# murdock_conn_v4.net
KiCad netlist of a schematic drawn in EAGLE
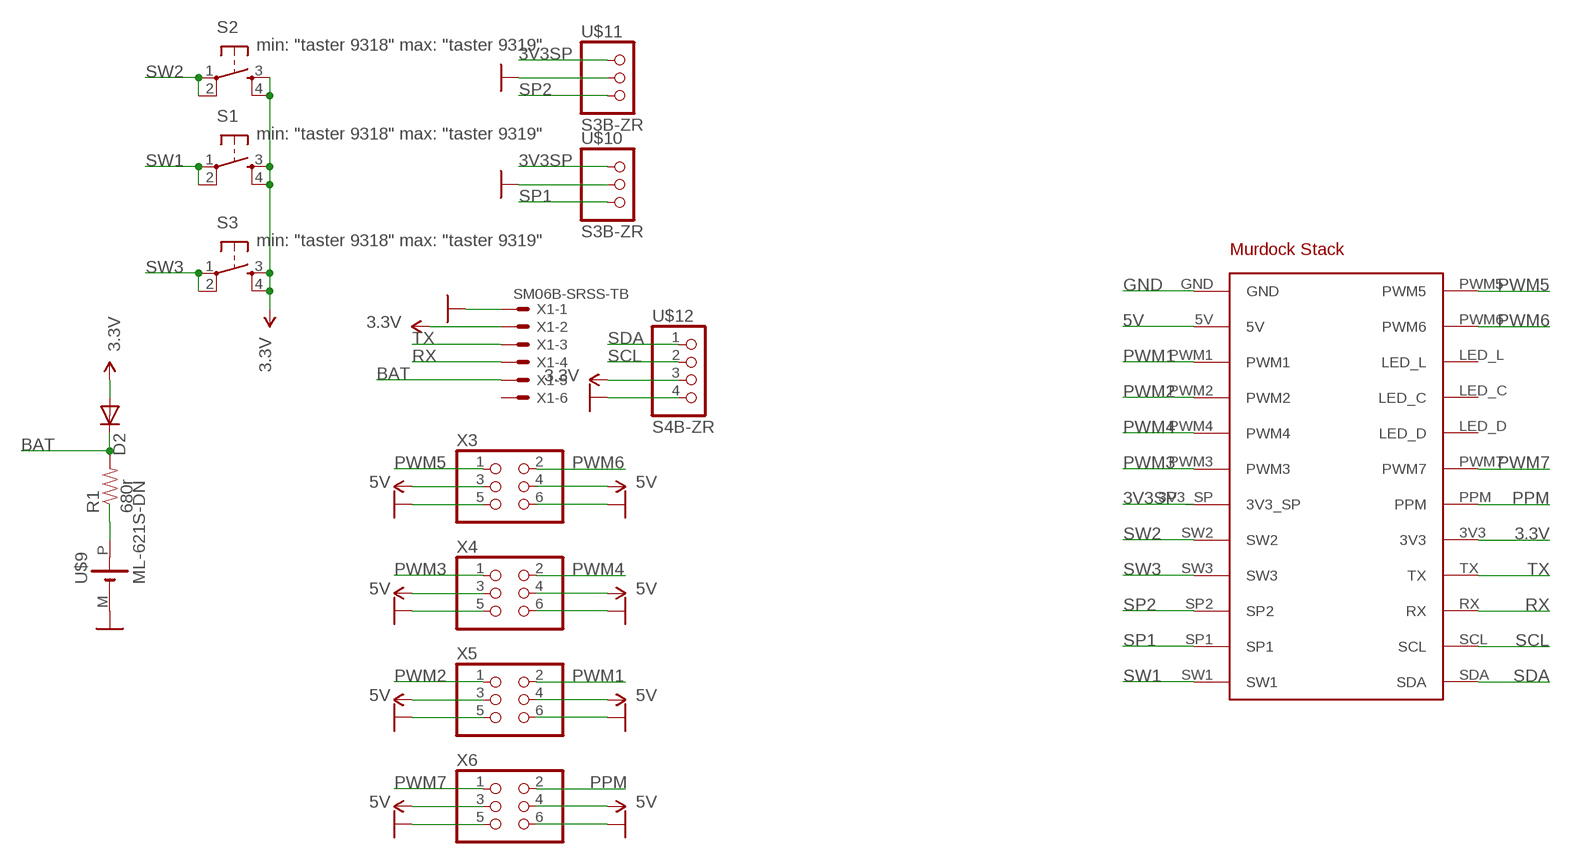
[diagram p0: schematic, sheet 1]

(export (version "E")
  (design (tool "Eeschema 10.0.6"))
  (components
    (comp (ref "D2")
      (value "DIODE-SOD323-R")
      (footprint "eagle-import:SOD323-R")
      (libsource (lib "eagle-import") (part "DIODE-SOD323-R"))
    )
    (comp (ref "R1")
      (value "680r")
      (footprint "eagle-import:0805")
      (libsource (lib "eagle-import") (part "RESISTOR0805-RES"))
    )
    (comp (ref "S1")
      (value "min: \"taster 9318\" max: \"taster 9319\"")
      (footprint "eagle-import:LSH")
      (libsource (lib "eagle-import") (part "LSH"))
    )
    (comp (ref "S2")
      (value "min: \"taster 9318\" max: \"taster 9319\"")
      (footprint "eagle-import:LSH")
      (libsource (lib "eagle-import") (part "LSH"))
    )
    (comp (ref "S3")
      (value "min: \"taster 9318\" max: \"taster 9319\"")
      (footprint "eagle-import:LSH")
      (libsource (lib "eagle-import") (part "LSH"))
    )
    (comp (ref "U$9")
      (value "ML-621S-DN")
      (footprint "eagle-import:ML-621S-DN")
      (libsource (lib "eagle-import") (part "ML-621S-DN"))
    )
    (comp (ref "U$10")
      (value "S3B-ZR")
      (footprint "eagle-import:S3B-ZR")
      (libsource (lib "eagle-import") (part "S3B-ZR"))
    )
    (comp (ref "U$11")
      (value "S3B-ZR")
      (footprint "eagle-import:S3B-ZR")
      (libsource (lib "eagle-import") (part "S3B-ZR"))
    )
    (comp (ref "U$12")
      (value "S4B-ZR")
      (footprint "eagle-import:S4B-ZR")
      (libsource (lib "eagle-import") (part "S4B-ZR"))
    )
    (comp (ref "X1")
      (value "SM06B-SRSS-TB")
      (footprint "eagle-import:SM06B-SRSS-TB")
      (libsource (lib "eagle-import") (part "?M06B-SRSS-TBS"))
    )
    (comp (ref "X3")
      (value "PINHD-2X3/90")
      (footprint "eagle-import:2X03_90")
      (libsource (lib "eagle-import") (part "PINHD-2X3/90"))
    )
    (comp (ref "X4")
      (value "PINHD-2X3/90")
      (footprint "eagle-import:2X03_90")
      (libsource (lib "eagle-import") (part "PINHD-2X3/90"))
    )
    (comp (ref "X5")
      (value "PINHD-2X3/90")
      (footprint "eagle-import:2X03_90")
      (libsource (lib "eagle-import") (part "PINHD-2X3/90"))
    )
    (comp (ref "X6")
      (value "PINHD-2X3/90")
      (footprint "eagle-import:2X03_90")
      (libsource (lib "eagle-import") (part "PINHD-2X3/90"))
    )
    (comp (ref "X7")
      (value "MURDOCK_STACK")
      (footprint "eagle-import:MURDOCK_STACK")
      (libsource (lib "eagle-import") (part "MURDOCK_STACK"))
    )
  )
  (nets
    (net (code "1") (name "/3V3SP") (class "Default")
      (node (ref "U$10") (pin "1") (pinfunction "1_1") (pintype "bidirectional"))
      (node (ref "U$11") (pin "1") (pinfunction "1_1") (pintype "bidirectional"))
      (node (ref "X7") (pin "3V3_SP") (pinfunction "3V3_SP_3V3_SP") (pintype "bidirectional"))
    )
    (net (code "2") (name "/BAT") (class "Default")
      (node (ref "D2") (pin "C") (pinfunction "C_C") (pintype "passive"))
      (node (ref "R1") (pin "2") (pinfunction "2_2") (pintype "passive"))
      (node (ref "X1") (pin "5") (pinfunction "S_5") (pintype "passive"))
    )
    (net (code "3") (name "/PPM") (class "Default")
      (node (ref "X6") (pin "2") (pinfunction "2_2") (pintype "passive"))
      (node (ref "X7") (pin "PPM") (pinfunction "PPM_PPM") (pintype "bidirectional"))
    )
    (net (code "4") (name "/PWM1") (class "Default")
      (node (ref "X5") (pin "2") (pinfunction "2_2") (pintype "passive"))
      (node (ref "X7") (pin "PWM1") (pinfunction "PWM1_PWM1") (pintype "bidirectional"))
    )
    (net (code "5") (name "/PWM2") (class "Default")
      (node (ref "X5") (pin "1") (pinfunction "1_1") (pintype "passive"))
      (node (ref "X7") (pin "PWM2") (pinfunction "PWM2_PWM2") (pintype "bidirectional"))
    )
    (net (code "6") (name "/PWM3") (class "Default")
      (node (ref "X4") (pin "1") (pinfunction "1_1") (pintype "passive"))
      (node (ref "X7") (pin "PWM3") (pinfunction "PWM3_PWM3") (pintype "bidirectional"))
    )
    (net (code "7") (name "/PWM4") (class "Default")
      (node (ref "X4") (pin "2") (pinfunction "2_2") (pintype "passive"))
      (node (ref "X7") (pin "PWM4") (pinfunction "PWM4_PWM4") (pintype "bidirectional"))
    )
    (net (code "8") (name "/PWM5") (class "Default")
      (node (ref "X3") (pin "1") (pinfunction "1_1") (pintype "passive"))
      (node (ref "X7") (pin "PWM5") (pinfunction "PWM5_PWM5") (pintype "bidirectional"))
    )
    (net (code "9") (name "/PWM6") (class "Default")
      (node (ref "X3") (pin "2") (pinfunction "2_2") (pintype "passive"))
      (node (ref "X7") (pin "PWM6") (pinfunction "PWM6_PWM6") (pintype "bidirectional"))
    )
    (net (code "10") (name "/PWM7") (class "Default")
      (node (ref "X6") (pin "1") (pinfunction "1_1") (pintype "passive"))
      (node (ref "X7") (pin "PWM7") (pinfunction "PWM7_PWM7") (pintype "bidirectional"))
    )
    (net (code "11") (name "/RX") (class "Default")
      (node (ref "X1") (pin "4") (pinfunction "S_4") (pintype "passive"))
      (node (ref "X7") (pin "RX") (pinfunction "RX_RX") (pintype "bidirectional"))
    )
    (net (code "12") (name "/SCL") (class "Default")
      (node (ref "U$12") (pin "2") (pinfunction "2_2") (pintype "power_in"))
      (node (ref "X7") (pin "SCL") (pinfunction "SCL_SCL") (pintype "bidirectional"))
    )
    (net (code "13") (name "/SDA") (class "Default")
      (node (ref "U$12") (pin "1") (pinfunction "1_1") (pintype "power_in"))
      (node (ref "X7") (pin "SDA") (pinfunction "SDA_SDA") (pintype "bidirectional"))
    )
    (net (code "14") (name "/SP1") (class "Default")
      (node (ref "U$10") (pin "3") (pinfunction "3_3") (pintype "bidirectional"))
      (node (ref "X7") (pin "SP1") (pinfunction "SP1_SP1") (pintype "bidirectional"))
    )
    (net (code "15") (name "/SP2") (class "Default")
      (node (ref "U$11") (pin "3") (pinfunction "3_3") (pintype "bidirectional"))
      (node (ref "X7") (pin "SP2") (pinfunction "SP2_SP2") (pintype "bidirectional"))
    )
    (net (code "16") (name "/SW1") (class "Default")
      (node (ref "S1") (pin "1") (pinfunction "1_1") (pintype "passive"))
      (node (ref "S1") (pin "2") (pinfunction "2_2") (pintype "passive"))
      (node (ref "X7") (pin "SW1") (pinfunction "SW1_SW1") (pintype "bidirectional"))
    )
    (net (code "17") (name "/SW2") (class "Default")
      (node (ref "S2") (pin "1") (pinfunction "1_1") (pintype "passive"))
      (node (ref "S2") (pin "2") (pinfunction "2_2") (pintype "passive"))
      (node (ref "X7") (pin "SW2") (pinfunction "SW2_SW2") (pintype "bidirectional"))
    )
    (net (code "18") (name "/SW3") (class "Default")
      (node (ref "S3") (pin "1") (pinfunction "1_1") (pintype "passive"))
      (node (ref "S3") (pin "2") (pinfunction "2_2") (pintype "passive"))
      (node (ref "X7") (pin "SW3") (pinfunction "SW3_SW3") (pintype "bidirectional"))
    )
    (net (code "19") (name "/TX") (class "Default")
      (node (ref "X1") (pin "3") (pinfunction "S_3") (pintype "passive"))
      (node (ref "X7") (pin "TX") (pinfunction "TX_TX") (pintype "bidirectional"))
    )
    (net (code "20") (name "3.3V") (class "Default")
      (node (ref "D2") (pin "A") (pinfunction "A_A") (pintype "passive"))
      (node (ref "S1") (pin "3") (pinfunction "3_3") (pintype "passive"))
      (node (ref "S1") (pin "4") (pinfunction "4_4") (pintype "passive"))
      (node (ref "S2") (pin "3") (pinfunction "3_3") (pintype "passive"))
      (node (ref "S2") (pin "4") (pinfunction "4_4") (pintype "passive"))
      (node (ref "S3") (pin "3") (pinfunction "3_3") (pintype "passive"))
      (node (ref "S3") (pin "4") (pinfunction "4_4") (pintype "passive"))
      (node (ref "U$12") (pin "3") (pinfunction "3_3") (pintype "power_in"))
      (node (ref "X1") (pin "2") (pinfunction "S_2") (pintype "passive"))
      (node (ref "X7") (pin "3V3") (pinfunction "3V3_3V3") (pintype "bidirectional"))
    )
    (net (code "21") (name "5V") (class "Default")
      (node (ref "X3") (pin "3") (pinfunction "3_3") (pintype "passive"))
      (node (ref "X3") (pin "4") (pinfunction "4_4") (pintype "passive"))
      (node (ref "X4") (pin "3") (pinfunction "3_3") (pintype "passive"))
      (node (ref "X4") (pin "4") (pinfunction "4_4") (pintype "passive"))
      (node (ref "X5") (pin "3") (pinfunction "3_3") (pintype "passive"))
      (node (ref "X5") (pin "4") (pinfunction "4_4") (pintype "passive"))
      (node (ref "X6") (pin "3") (pinfunction "3_3") (pintype "passive"))
      (node (ref "X6") (pin "4") (pinfunction "4_4") (pintype "passive"))
      (node (ref "X7") (pin "5V") (pinfunction "5V_5V") (pintype "bidirectional"))
    )
    (net (code "22") (name "GND") (class "Default")
      (node (ref "U$10") (pin "2") (pinfunction "2_2") (pintype "bidirectional"))
      (node (ref "U$11") (pin "2") (pinfunction "2_2") (pintype "bidirectional"))
      (node (ref "U$12") (pin "4") (pinfunction "4_4") (pintype "power_in"))
      (node (ref "U$9") (pin "M") (pinfunction "-_M") (pintype "passive"))
      (node (ref "X1") (pin "1") (pinfunction "S_1") (pintype "passive"))
      (node (ref "X3") (pin "5") (pinfunction "5_5") (pintype "passive"))
      (node (ref "X3") (pin "6") (pinfunction "6_6") (pintype "passive"))
      (node (ref "X4") (pin "5") (pinfunction "5_5") (pintype "passive"))
      (node (ref "X4") (pin "6") (pinfunction "6_6") (pintype "passive"))
      (node (ref "X5") (pin "5") (pinfunction "5_5") (pintype "passive"))
      (node (ref "X5") (pin "6") (pinfunction "6_6") (pintype "passive"))
      (node (ref "X6") (pin "5") (pinfunction "5_5") (pintype "passive"))
      (node (ref "X6") (pin "6") (pinfunction "6_6") (pintype "passive"))
      (node (ref "X7") (pin "GND") (pinfunction "GND_GND") (pintype "bidirectional"))
    )
    (net (code "23") (name "Net-(U$9-+)") (class "Default")
      (node (ref "R1") (pin "1") (pinfunction "1_1") (pintype "passive"))
      (node (ref "U$9") (pin "P") (pinfunction "+_P") (pintype "passive"))
    )
    (net (code "24") (name "unconnected-(X1F-S-Pad6)") (class "Default")
      (node (ref "X1") (pin "6") (pinfunction "S_6") (pintype "passive"))
    )
    (net (code "25") (name "unconnected-(X7-PadLED_C)") (class "Default")
      (node (ref "X7") (pin "LED_C") (pinfunction "LED_C_LED_C") (pintype "bidirectional"))
    )
    (net (code "26") (name "unconnected-(X7-PadLED_D)") (class "Default")
      (node (ref "X7") (pin "LED_D") (pinfunction "LED_D_LED_D") (pintype "bidirectional"))
    )
    (net (code "27") (name "unconnected-(X7-PadLED_L)") (class "Default")
      (node (ref "X7") (pin "LED_L") (pinfunction "LED_L_LED_L") (pintype "bidirectional"))
    )
  )
)
